# Configuration_Power.net
KiCad netlist of a schematic drawn in Altium Designer
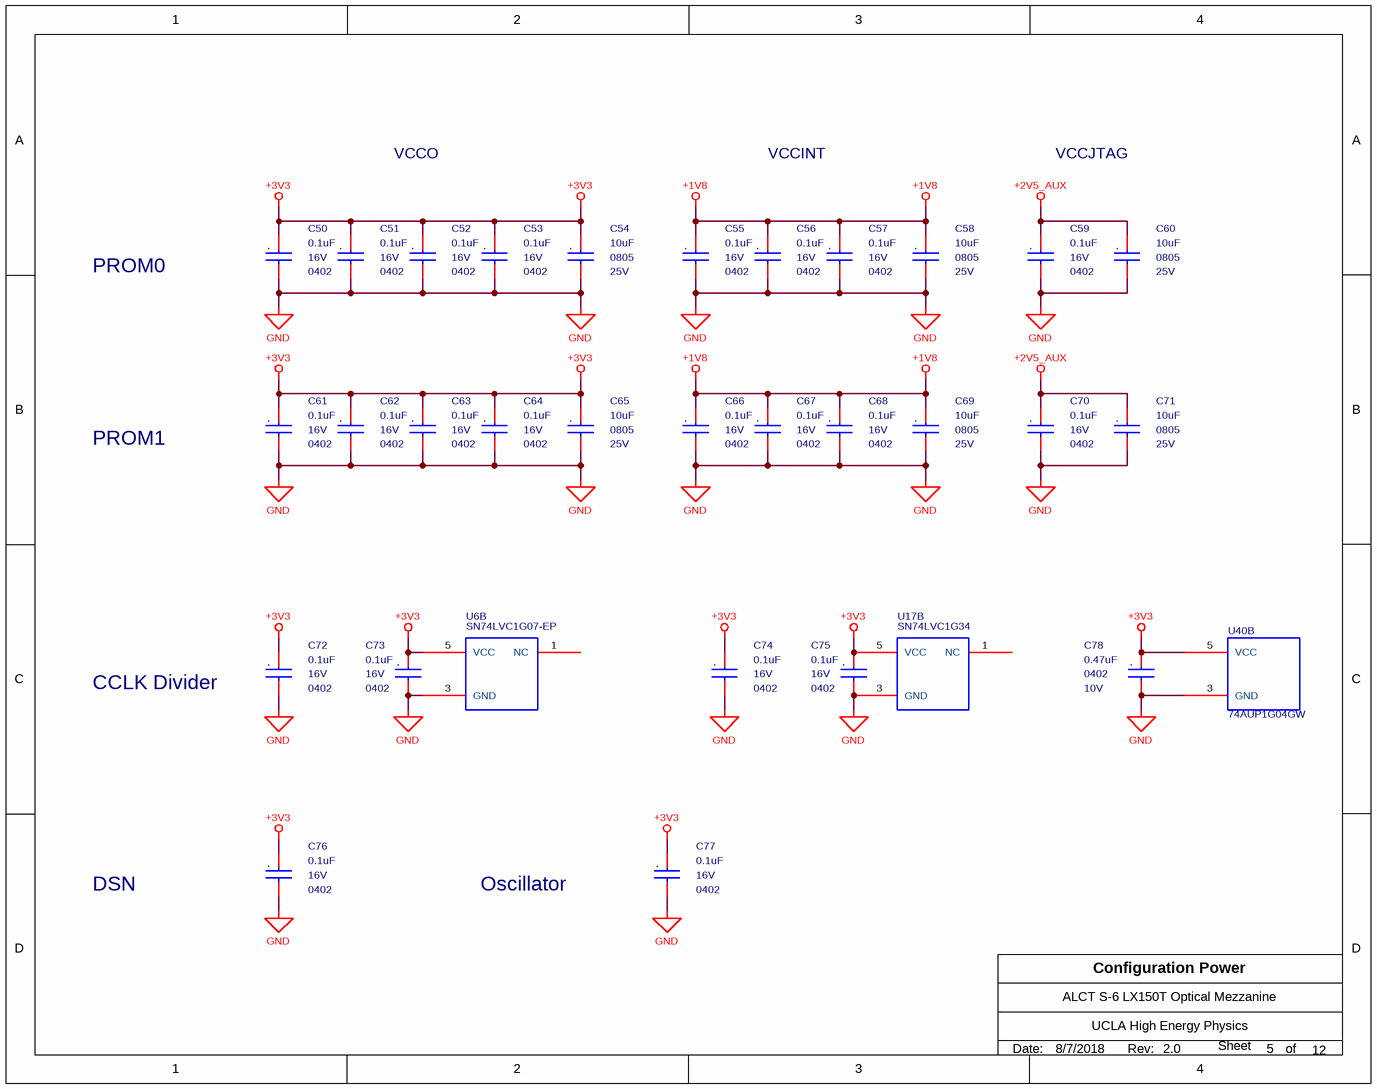
[diagram p0: Configuration_Power.SchDoc]

(export (version "E")
  (design (tool "Eeschema 10.0.6"))
  (components
    (comp (ref "C50")
      (value "0.1uF")
      (footprint "MC_S6/SM/C_0402_IPC")
      (description "CAP CER 0.1UF 16V X7R 0402")
      (fields
        (field (name "MANUFACTURER") "KEMET")
        (field (name "MANUFACTURER PART NUMBER") "C0402C104K4RACTU")
        (field (name "PACKAGE") "0402")
        (field (name "VOLTAGE - RATED") "16V")
      )
      (libsource (lib "ALCT_MEZ_SPARTAN6_Library") (part "C0402C104K4RACTU"))
    )
    (comp (ref "C51")
      (value "0.1uF")
      (footprint "MC_S6/SM/C_0402_IPC")
      (description "CAP CER 0.1UF 16V X7R 0402")
      (fields
        (field (name "MANUFACTURER") "KEMET")
        (field (name "MANUFACTURER PART NUMBER") "C0402C104K4RACTU")
        (field (name "PACKAGE") "0402")
        (field (name "VOLTAGE - RATED") "16V")
      )
      (libsource (lib "ALCT_MEZ_SPARTAN6_Library") (part "C0402C104K4RACTU"))
    )
    (comp (ref "C52")
      (value "0.1uF")
      (footprint "MC_S6/SM/C_0402_IPC")
      (description "CAP CER 0.1UF 16V X7R 0402")
      (fields
        (field (name "MANUFACTURER") "KEMET")
        (field (name "MANUFACTURER PART NUMBER") "C0402C104K4RACTU")
        (field (name "PACKAGE") "0402")
        (field (name "VOLTAGE - RATED") "16V")
      )
      (libsource (lib "ALCT_MEZ_SPARTAN6_Library") (part "C0402C104K4RACTU"))
    )
    (comp (ref "C53")
      (value "0.1uF")
      (footprint "MC_S6/SM/C_0402_IPC")
      (description "CAP CER 0.1UF 16V X7R 0402")
      (fields
        (field (name "MANUFACTURER") "KEMET")
        (field (name "MANUFACTURER PART NUMBER") "C0402C104K4RACTU")
        (field (name "PACKAGE") "0402")
        (field (name "VOLTAGE - RATED") "16V")
      )
      (libsource (lib "ALCT_MEZ_SPARTAN6_Library") (part "C0402C104K4RACTU"))
    )
    (comp (ref "C54")
      (value "10uF")
      (footprint "MC_S6/SM/C_0805_IPC")
      (description "CAP CER 10UF 25V X5R 0805")
      (fields
        (field (name "MANUFACTURER") "Murata Electronics North America")
        (field (name "MANUFACTURER PART NUMBER") "GRM21BR61E106KA73L")
        (field (name "VOLTAGE - RATED") "25V")
        (field (name "PACKAGE") "0805")
      )
      (libsource (lib "ALCT_MEZ_SPARTAN6_Library") (part "GRM21BR61E106KA73L"))
    )
    (comp (ref "C55")
      (value "0.1uF")
      (footprint "MC_S6/SM/C_0402_IPC")
      (description "CAP CER 0.1UF 16V X7R 0402")
      (fields
        (field (name "MANUFACTURER") "KEMET")
        (field (name "MANUFACTURER PART NUMBER") "C0402C104K4RACTU")
        (field (name "PACKAGE") "0402")
        (field (name "VOLTAGE - RATED") "16V")
      )
      (libsource (lib "ALCT_MEZ_SPARTAN6_Library") (part "C0402C104K4RACTU"))
    )
    (comp (ref "C56")
      (value "0.1uF")
      (footprint "MC_S6/SM/C_0402_IPC")
      (description "CAP CER 0.1UF 16V X7R 0402")
      (fields
        (field (name "MANUFACTURER") "KEMET")
        (field (name "MANUFACTURER PART NUMBER") "C0402C104K4RACTU")
        (field (name "PACKAGE") "0402")
        (field (name "VOLTAGE - RATED") "16V")
      )
      (libsource (lib "ALCT_MEZ_SPARTAN6_Library") (part "C0402C104K4RACTU"))
    )
    (comp (ref "C57")
      (value "0.1uF")
      (footprint "MC_S6/SM/C_0402_IPC")
      (description "CAP CER 0.1UF 16V X7R 0402")
      (fields
        (field (name "MANUFACTURER") "KEMET")
        (field (name "MANUFACTURER PART NUMBER") "C0402C104K4RACTU")
        (field (name "PACKAGE") "0402")
        (field (name "VOLTAGE - RATED") "16V")
      )
      (libsource (lib "ALCT_MEZ_SPARTAN6_Library") (part "C0402C104K4RACTU"))
    )
    (comp (ref "C58")
      (value "10uF")
      (footprint "MC_S6/SM/C_0805_IPC")
      (description "CAP CER 10UF 25V X5R 0805")
      (fields
        (field (name "MANUFACTURER") "Murata Electronics North America")
        (field (name "MANUFACTURER PART NUMBER") "GRM21BR61E106KA73L")
        (field (name "VOLTAGE - RATED") "25V")
        (field (name "PACKAGE") "0805")
      )
      (libsource (lib "ALCT_MEZ_SPARTAN6_Library") (part "GRM21BR61E106KA73L"))
    )
    (comp (ref "C59")
      (value "0.1uF")
      (footprint "MC_S6/SM/C_0402_IPC")
      (description "CAP CER 0.1UF 16V X7R 0402")
      (fields
        (field (name "MANUFACTURER") "KEMET")
        (field (name "MANUFACTURER PART NUMBER") "C0402C104K4RACTU")
        (field (name "PACKAGE") "0402")
        (field (name "VOLTAGE - RATED") "16V")
      )
      (libsource (lib "ALCT_MEZ_SPARTAN6_Library") (part "C0402C104K4RACTU"))
    )
    (comp (ref "C60")
      (value "10uF")
      (footprint "MC_S6/SM/C_0805_IPC")
      (description "CAP CER 10UF 25V X5R 0805")
      (fields
        (field (name "MANUFACTURER") "Murata Electronics North America")
        (field (name "MANUFACTURER PART NUMBER") "GRM21BR61E106KA73L")
        (field (name "VOLTAGE - RATED") "25V")
        (field (name "PACKAGE") "0805")
      )
      (libsource (lib "ALCT_MEZ_SPARTAN6_Library") (part "GRM21BR61E106KA73L"))
    )
    (comp (ref "C61")
      (value "0.1uF")
      (footprint "MC_S6/SM/C_0402_IPC")
      (description "CAP CER 0.1UF 16V X7R 0402")
      (fields
        (field (name "MANUFACTURER") "KEMET")
        (field (name "MANUFACTURER PART NUMBER") "C0402C104K4RACTU")
        (field (name "PACKAGE") "0402")
        (field (name "VOLTAGE - RATED") "16V")
      )
      (libsource (lib "ALCT_MEZ_SPARTAN6_Library") (part "C0402C104K4RACTU"))
    )
    (comp (ref "C62")
      (value "0.1uF")
      (footprint "MC_S6/SM/C_0402_IPC")
      (description "CAP CER 0.1UF 16V X7R 0402")
      (fields
        (field (name "MANUFACTURER") "KEMET")
        (field (name "MANUFACTURER PART NUMBER") "C0402C104K4RACTU")
        (field (name "PACKAGE") "0402")
        (field (name "VOLTAGE - RATED") "16V")
      )
      (libsource (lib "ALCT_MEZ_SPARTAN6_Library") (part "C0402C104K4RACTU"))
    )
    (comp (ref "C63")
      (value "0.1uF")
      (footprint "MC_S6/SM/C_0402_IPC")
      (description "CAP CER 0.1UF 16V X7R 0402")
      (fields
        (field (name "MANUFACTURER") "KEMET")
        (field (name "MANUFACTURER PART NUMBER") "C0402C104K4RACTU")
        (field (name "PACKAGE") "0402")
        (field (name "VOLTAGE - RATED") "16V")
      )
      (libsource (lib "ALCT_MEZ_SPARTAN6_Library") (part "C0402C104K4RACTU"))
    )
    (comp (ref "C64")
      (value "0.1uF")
      (footprint "MC_S6/SM/C_0402_IPC")
      (description "CAP CER 0.1UF 16V X7R 0402")
      (fields
        (field (name "MANUFACTURER") "KEMET")
        (field (name "MANUFACTURER PART NUMBER") "C0402C104K4RACTU")
        (field (name "PACKAGE") "0402")
        (field (name "VOLTAGE - RATED") "16V")
      )
      (libsource (lib "ALCT_MEZ_SPARTAN6_Library") (part "C0402C104K4RACTU"))
    )
    (comp (ref "C65")
      (value "10uF")
      (footprint "MC_S6/SM/C_0805_IPC")
      (description "CAP CER 10UF 25V X5R 0805")
      (fields
        (field (name "MANUFACTURER") "Murata Electronics North America")
        (field (name "MANUFACTURER PART NUMBER") "GRM21BR61E106KA73L")
        (field (name "VOLTAGE - RATED") "25V")
        (field (name "PACKAGE") "0805")
      )
      (libsource (lib "ALCT_MEZ_SPARTAN6_Library") (part "GRM21BR61E106KA73L"))
    )
    (comp (ref "C66")
      (value "0.1uF")
      (footprint "MC_S6/SM/C_0402_IPC")
      (description "CAP CER 0.1UF 16V X7R 0402")
      (fields
        (field (name "MANUFACTURER") "KEMET")
        (field (name "MANUFACTURER PART NUMBER") "C0402C104K4RACTU")
        (field (name "PACKAGE") "0402")
        (field (name "VOLTAGE - RATED") "16V")
      )
      (libsource (lib "ALCT_MEZ_SPARTAN6_Library") (part "C0402C104K4RACTU"))
    )
    (comp (ref "C67")
      (value "0.1uF")
      (footprint "MC_S6/SM/C_0402_IPC")
      (description "CAP CER 0.1UF 16V X7R 0402")
      (fields
        (field (name "MANUFACTURER") "KEMET")
        (field (name "MANUFACTURER PART NUMBER") "C0402C104K4RACTU")
        (field (name "PACKAGE") "0402")
        (field (name "VOLTAGE - RATED") "16V")
      )
      (libsource (lib "ALCT_MEZ_SPARTAN6_Library") (part "C0402C104K4RACTU"))
    )
    (comp (ref "C68")
      (value "0.1uF")
      (footprint "MC_S6/SM/C_0402_IPC")
      (description "CAP CER 0.1UF 16V X7R 0402")
      (fields
        (field (name "MANUFACTURER") "KEMET")
        (field (name "MANUFACTURER PART NUMBER") "C0402C104K4RACTU")
        (field (name "PACKAGE") "0402")
        (field (name "VOLTAGE - RATED") "16V")
      )
      (libsource (lib "ALCT_MEZ_SPARTAN6_Library") (part "C0402C104K4RACTU"))
    )
    (comp (ref "C69")
      (value "10uF")
      (footprint "MC_S6/SM/C_0805_IPC")
      (description "CAP CER 10UF 25V X5R 0805")
      (fields
        (field (name "MANUFACTURER") "Murata Electronics North America")
        (field (name "MANUFACTURER PART NUMBER") "GRM21BR61E106KA73L")
        (field (name "VOLTAGE - RATED") "25V")
        (field (name "PACKAGE") "0805")
      )
      (libsource (lib "ALCT_MEZ_SPARTAN6_Library") (part "GRM21BR61E106KA73L"))
    )
    (comp (ref "C70")
      (value "0.1uF")
      (footprint "MC_S6/SM/C_0402_IPC")
      (description "CAP CER 0.1UF 16V X7R 0402")
      (fields
        (field (name "MANUFACTURER") "KEMET")
        (field (name "MANUFACTURER PART NUMBER") "C0402C104K4RACTU")
        (field (name "PACKAGE") "0402")
        (field (name "VOLTAGE - RATED") "16V")
      )
      (libsource (lib "ALCT_MEZ_SPARTAN6_Library") (part "C0402C104K4RACTU"))
    )
    (comp (ref "C71")
      (value "10uF")
      (footprint "MC_S6/SM/C_0805_IPC")
      (description "CAP CER 10UF 25V X5R 0805")
      (fields
        (field (name "MANUFACTURER") "Murata Electronics North America")
        (field (name "MANUFACTURER PART NUMBER") "GRM21BR61E106KA73L")
        (field (name "VOLTAGE - RATED") "25V")
        (field (name "PACKAGE") "0805")
      )
      (libsource (lib "ALCT_MEZ_SPARTAN6_Library") (part "GRM21BR61E106KA73L"))
    )
    (comp (ref "C72")
      (value "0.1uF")
      (footprint "MC_S6/SM/C_0402_IPC")
      (description "CAP CER 0.1UF 16V X7R 0402")
      (fields
        (field (name "MANUFACTURER") "KEMET")
        (field (name "MANUFACTURER PART NUMBER") "C0402C104K4RACTU")
        (field (name "PACKAGE") "0402")
        (field (name "VOLTAGE - RATED") "16V")
      )
      (libsource (lib "ALCT_MEZ_SPARTAN6_Library") (part "C0402C104K4RACTU"))
    )
    (comp (ref "C73")
      (value "0.1uF")
      (footprint "MC_S6/SM/C_0402_IPC")
      (description "CAP CER 0.1UF 16V X7R 0402")
      (fields
        (field (name "MANUFACTURER") "KEMET")
        (field (name "MANUFACTURER PART NUMBER") "C0402C104K4RACTU")
        (field (name "PACKAGE") "0402")
        (field (name "VOLTAGE - RATED") "16V")
      )
      (libsource (lib "ALCT_MEZ_SPARTAN6_Library") (part "C0402C104K4RACTU"))
    )
    (comp (ref "C74")
      (value "0.1uF")
      (footprint "MC_S6/SM/C_0402_IPC")
      (description "CAP CER 0.1UF 16V X7R 0402")
      (fields
        (field (name "MANUFACTURER") "KEMET")
        (field (name "MANUFACTURER PART NUMBER") "C0402C104K4RACTU")
        (field (name "PACKAGE") "0402")
        (field (name "VOLTAGE - RATED") "16V")
      )
      (libsource (lib "ALCT_MEZ_SPARTAN6_Library") (part "C0402C104K4RACTU"))
    )
    (comp (ref "C75")
      (value "0.1uF")
      (footprint "MC_S6/SM/C_0402_IPC")
      (description "CAP CER 0.1UF 16V X7R 0402")
      (fields
        (field (name "MANUFACTURER") "KEMET")
        (field (name "MANUFACTURER PART NUMBER") "C0402C104K4RACTU")
        (field (name "PACKAGE") "0402")
        (field (name "VOLTAGE - RATED") "16V")
      )
      (libsource (lib "ALCT_MEZ_SPARTAN6_Library") (part "C0402C104K4RACTU"))
    )
    (comp (ref "C76")
      (value "0.1uF")
      (footprint "MC_S6/SM/C_0402_IPC")
      (description "CAP CER 0.1UF 16V X7R 0402")
      (fields
        (field (name "MANUFACTURER") "KEMET")
        (field (name "MANUFACTURER PART NUMBER") "C0402C104K4RACTU")
        (field (name "PACKAGE") "0402")
        (field (name "VOLTAGE - RATED") "16V")
      )
      (libsource (lib "ALCT_MEZ_SPARTAN6_Library") (part "C0402C104K4RACTU"))
    )
    (comp (ref "C77")
      (value "0.1uF")
      (footprint "MC_S6/SM/C_0402_IPC")
      (description "CAP CER 0.1UF 16V X7R 0402")
      (fields
        (field (name "MANUFACTURER") "KEMET")
        (field (name "MANUFACTURER PART NUMBER") "C0402C104K4RACTU")
        (field (name "PACKAGE") "0402")
        (field (name "VOLTAGE - RATED") "16V")
      )
      (libsource (lib "ALCT_MEZ_SPARTAN6_Library") (part "C0402C104K4RACTU"))
    )
    (comp (ref "C78")
      (value "0.47uF")
      (footprint "MC_S6/SM/C_0402_IPC")
      (description "CAP CER 0.47UF 10V X5R 0402")
      (fields
        (field (name "MANUFACTURER") "Murata Electronics North America")
        (field (name "MANUFACTURER PART NUMBER") "GRM155R61A474KE15J")
        (field (name "VOLTAGE - RATED") "10V")
        (field (name "PACKAGE") "0402")
      )
      (libsource (lib "ALCT_MEZ_SPARTAN6_Library") (part "GRM155R61A474KE15J"))
    )
    (comp (ref "U6")
      (value "SN74LVC1G07-EP")
      (footprint "MC_S6/SM/SOT_SC70_DCK5")
      (fields
        (field (name "MANUFACTURER") "Texas Instruments")
        (field (name "MANUFACTURER PART NUMBER") "SN74LVC1G07MDCKREP")
      )
      (libsource (lib "ALCT_MEZ_SPARTAN6_Library") (part "SN74LVC1G07-EP"))
    )
    (comp (ref "U17")
      (value "SN74LVC1G34")
      (footprint "MC_S6/SM/SOT_553_DRL5")
      (description "IC BUFFER NON-INVERT SOT5")
      (fields
        (field (name "MANUFACTURER") "Texas Instruments")
        (field (name "MANUFACTURER PART NUMBER") "SN74LVC1G34DRLR")
      )
      (libsource (lib "ALCT_MEZ_SPARTAN6_Library") (part "SN74LVC1G34DRLR"))
    )
    (comp (ref "U40")
      (value "74AUP1G04GW")
      (footprint "SOT353-1")
      (description "IC INVERTER LP 5TSSOP")
      (fields
        (field (name "MANUFACTURER") "Nexperia USA Inc.")
        (field (name "MANUFACTURER PART NUMBER") "74AUP1G04GW,125")
      )
      (libsource (lib "ALCT_MEZ_SPARTAN6_Library") (part "74AUP1G04GW"))
    )
  )
  (nets
    (net (code "1") (name "+1V8") (class "Default")
      (node (ref "C55") (pin "1") (pinfunction "1_1") (pintype "passive"))
      (node (ref "C56") (pin "1") (pinfunction "1_1") (pintype "passive"))
      (node (ref "C57") (pin "1") (pinfunction "1_1") (pintype "passive"))
      (node (ref "C58") (pin "1") (pinfunction "1_1") (pintype "passive"))
      (node (ref "C66") (pin "1") (pinfunction "1_1") (pintype "passive"))
      (node (ref "C67") (pin "1") (pinfunction "1_1") (pintype "passive"))
      (node (ref "C68") (pin "1") (pinfunction "1_1") (pintype "passive"))
      (node (ref "C69") (pin "1") (pinfunction "1_1") (pintype "passive"))
    )
    (net (code "2") (name "+2V5_AUX") (class "Default")
      (node (ref "C59") (pin "1") (pinfunction "1_1") (pintype "passive"))
      (node (ref "C60") (pin "1") (pinfunction "1_1") (pintype "passive"))
      (node (ref "C70") (pin "1") (pinfunction "1_1") (pintype "passive"))
      (node (ref "C71") (pin "1") (pinfunction "1_1") (pintype "passive"))
    )
    (net (code "3") (name "+3V3") (class "Default")
      (node (ref "C50") (pin "1") (pinfunction "1_1") (pintype "passive"))
      (node (ref "C51") (pin "1") (pinfunction "1_1") (pintype "passive"))
      (node (ref "C52") (pin "1") (pinfunction "1_1") (pintype "passive"))
      (node (ref "C53") (pin "1") (pinfunction "1_1") (pintype "passive"))
      (node (ref "C54") (pin "1") (pinfunction "1_1") (pintype "passive"))
      (node (ref "C61") (pin "1") (pinfunction "1_1") (pintype "passive"))
      (node (ref "C62") (pin "1") (pinfunction "1_1") (pintype "passive"))
      (node (ref "C63") (pin "1") (pinfunction "1_1") (pintype "passive"))
      (node (ref "C64") (pin "1") (pinfunction "1_1") (pintype "passive"))
      (node (ref "C65") (pin "1") (pinfunction "1_1") (pintype "passive"))
      (node (ref "C72") (pin "1") (pinfunction "1_1") (pintype "passive"))
      (node (ref "C73") (pin "1") (pinfunction "1_1") (pintype "passive"))
      (node (ref "C74") (pin "1") (pinfunction "1_1") (pintype "passive"))
      (node (ref "C75") (pin "1") (pinfunction "1_1") (pintype "passive"))
      (node (ref "C76") (pin "1") (pinfunction "1_1") (pintype "passive"))
      (node (ref "C77") (pin "1") (pinfunction "1_1") (pintype "passive"))
      (node (ref "C78") (pin "1") (pinfunction "1_1") (pintype "passive"))
      (node (ref "U17") (pin "5") (pinfunction "VCC_5") (pintype "power_in"))
      (node (ref "U40") (pin "5") (pinfunction "VCC_5") (pintype "power_in"))
      (node (ref "U6") (pin "5") (pinfunction "VCC_5") (pintype "power_in"))
    )
    (net (code "4") (name "GND") (class "Default")
      (node (ref "C50") (pin "2") (pinfunction "2_2") (pintype "passive"))
      (node (ref "C51") (pin "2") (pinfunction "2_2") (pintype "passive"))
      (node (ref "C52") (pin "2") (pinfunction "2_2") (pintype "passive"))
      (node (ref "C53") (pin "2") (pinfunction "2_2") (pintype "passive"))
      (node (ref "C54") (pin "2") (pinfunction "2_2") (pintype "passive"))
      (node (ref "C55") (pin "2") (pinfunction "2_2") (pintype "passive"))
      (node (ref "C56") (pin "2") (pinfunction "2_2") (pintype "passive"))
      (node (ref "C57") (pin "2") (pinfunction "2_2") (pintype "passive"))
      (node (ref "C58") (pin "2") (pinfunction "2_2") (pintype "passive"))
      (node (ref "C59") (pin "2") (pinfunction "2_2") (pintype "passive"))
      (node (ref "C60") (pin "2") (pinfunction "2_2") (pintype "passive"))
      (node (ref "C61") (pin "2") (pinfunction "2_2") (pintype "passive"))
      (node (ref "C62") (pin "2") (pinfunction "2_2") (pintype "passive"))
      (node (ref "C63") (pin "2") (pinfunction "2_2") (pintype "passive"))
      (node (ref "C64") (pin "2") (pinfunction "2_2") (pintype "passive"))
      (node (ref "C65") (pin "2") (pinfunction "2_2") (pintype "passive"))
      (node (ref "C66") (pin "2") (pinfunction "2_2") (pintype "passive"))
      (node (ref "C67") (pin "2") (pinfunction "2_2") (pintype "passive"))
      (node (ref "C68") (pin "2") (pinfunction "2_2") (pintype "passive"))
      (node (ref "C69") (pin "2") (pinfunction "2_2") (pintype "passive"))
      (node (ref "C70") (pin "2") (pinfunction "2_2") (pintype "passive"))
      (node (ref "C71") (pin "2") (pinfunction "2_2") (pintype "passive"))
      (node (ref "C72") (pin "2") (pinfunction "2_2") (pintype "passive"))
      (node (ref "C73") (pin "2") (pinfunction "2_2") (pintype "passive"))
      (node (ref "C74") (pin "2") (pinfunction "2_2") (pintype "passive"))
      (node (ref "C75") (pin "2") (pinfunction "2_2") (pintype "passive"))
      (node (ref "C76") (pin "2") (pinfunction "2_2") (pintype "passive"))
      (node (ref "C77") (pin "2") (pinfunction "2_2") (pintype "passive"))
      (node (ref "C78") (pin "2") (pinfunction "2_2") (pintype "passive"))
      (node (ref "U17") (pin "3") (pinfunction "GND_3") (pintype "power_in"))
      (node (ref "U40") (pin "3") (pinfunction "GND_3") (pintype "power_in"))
      (node (ref "U6") (pin "3") (pinfunction "GND_3") (pintype "power_in"))
    )
    (net (code "5") (name "unconnected-(U6B-NC-Pad1)") (class "Default")
      (node (ref "U6") (pin "1") (pinfunction "NC_1") (pintype "passive"))
    )
    (net (code "6") (name "unconnected-(U17B-NC-Pad1)") (class "Default")
      (node (ref "U17") (pin "1") (pinfunction "NC_1") (pintype "passive"))
    )
  )
)
